# PCA9536.net
KiCad netlist of a schematic drawn in EAGLE
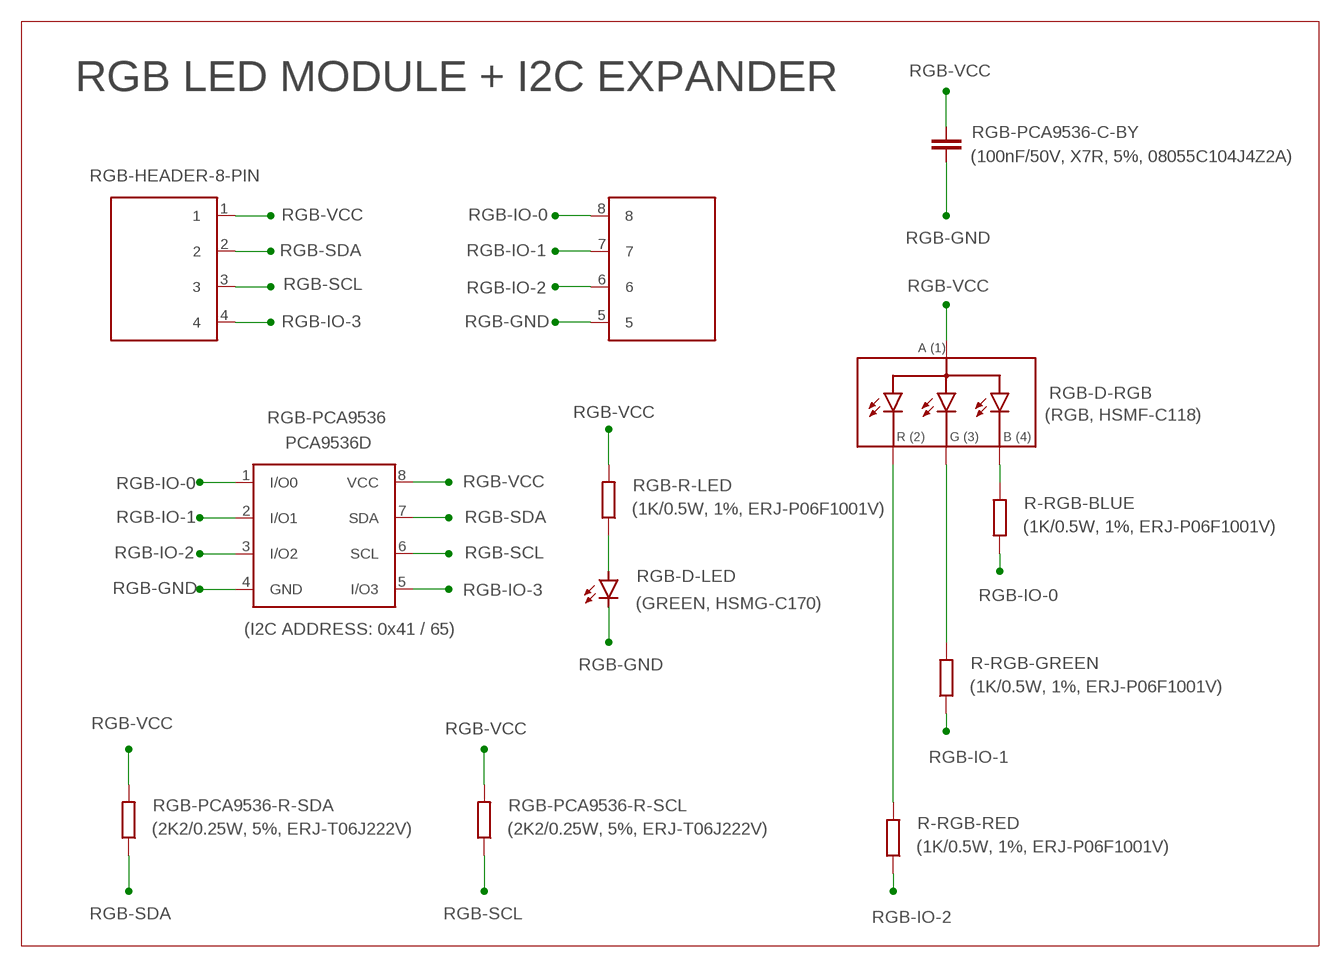
[diagram p0: schematic, sheet 1]

(export (version "E")
  (design (tool "Eeschema 10.0.6"))
  (components
    (comp (ref "R-RGB-BLUE")
      (value "(1K/0.5W, 1%, ERJ-P06F1001V)")
      (footprint "eagle-import:0805")
      (libsource (lib "eagle-import") (part "ERJ-P06F1001V"))
    )
    (comp (ref "R-RGB-GREEN")
      (value "(1K/0.5W, 1%, ERJ-P06F1001V)")
      (footprint "eagle-import:0805")
      (libsource (lib "eagle-import") (part "ERJ-P06F1001V"))
    )
    (comp (ref "R-RGB-RED")
      (value "(1K/0.5W, 1%, ERJ-P06F1001V)")
      (footprint "eagle-import:0805")
      (libsource (lib "eagle-import") (part "ERJ-P06F1001V"))
    )
    (comp (ref "RGB-D-LED")
      (value "(GREEN, HSMG-C170)")
      (footprint "eagle-import:DIODE_0805")
      (libsource (lib "eagle-import") (part "HSMG-C170"))
    )
    (comp (ref "RGB-D-RGB")
      (value "(RGB, HSMF-C118)")
      (footprint "eagle-import:DIODE_LED_1210_RGB")
      (libsource (lib "eagle-import") (part "HSMF-C118"))
    )
    (comp (ref "RGB-J1")
      (value "RGB-HEADER-8-PIN")
      (footprint "eagle-import:HEADER_2.54MM_8_PIN_VER")
      (libsource (lib "eagle-import") (part "HEADER_8_PIN"))
    )
    (comp (ref "RGB-PCA9536")
      (value "PCA9536D")
      (footprint "eagle-import:SOIC-8-NARROW")
      (libsource (lib "eagle-import") (part "PCA9536D"))
    )
    (comp (ref "RGB-PCA9536-C-BY")
      (value "(100nF/50V, X7R, 5%, 08055C104J4Z2A)")
      (footprint "eagle-import:0805")
      (libsource (lib "eagle-import") (part "08055C104J4Z2A"))
    )
    (comp (ref "RGB-PCA9536-R-SCL")
      (value "(2K2/0.25W, 5%, ERJ-T06J222V)")
      (footprint "eagle-import:0805")
      (libsource (lib "eagle-import") (part "ERJ-T06J222V"))
    )
    (comp (ref "RGB-PCA9536-R-SDA")
      (value "(2K2/0.25W, 5%, ERJ-T06J222V)")
      (footprint "eagle-import:0805")
      (libsource (lib "eagle-import") (part "ERJ-T06J222V"))
    )
    (comp (ref "RGB-R-LED")
      (value "(1K/0.5W, 1%, ERJ-P06F1001V)")
      (footprint "eagle-import:0805")
      (libsource (lib "eagle-import") (part "ERJ-P06F1001V"))
    )
  )
  (nets
    (net (code "1") (name "/RGB-GND") (class "Default")
      (node (ref "RGB-D-LED") (pin "C") (pinfunction "C_C") (pintype "passive"))
      (node (ref "RGB-J1") (pin "5") (pinfunction "5_5") (pintype "bidirectional"))
      (node (ref "RGB-PCA9536") (pin "4") (pinfunction "GND_4") (pintype "power_in"))
      (node (ref "RGB-PCA9536-C-BY") (pin "1") (pinfunction "A_1") (pintype "passive"))
    )
    (net (code "2") (name "/RGB-IO-0") (class "Default")
      (node (ref "R-RGB-BLUE") (pin "1") (pinfunction "1_1") (pintype "passive"))
      (node (ref "RGB-J1") (pin "8") (pinfunction "8_8") (pintype "bidirectional"))
      (node (ref "RGB-PCA9536") (pin "1") (pinfunction "I/O0_1") (pintype "bidirectional"))
    )
    (net (code "3") (name "/RGB-IO-1") (class "Default")
      (node (ref "R-RGB-GREEN") (pin "1") (pinfunction "1_1") (pintype "passive"))
      (node (ref "RGB-J1") (pin "7") (pinfunction "7_7") (pintype "bidirectional"))
      (node (ref "RGB-PCA9536") (pin "2") (pinfunction "I/O1_2") (pintype "bidirectional"))
    )
    (net (code "4") (name "/RGB-IO-2") (class "Default")
      (node (ref "R-RGB-RED") (pin "1") (pinfunction "1_1") (pintype "passive"))
      (node (ref "RGB-J1") (pin "6") (pinfunction "6_6") (pintype "bidirectional"))
      (node (ref "RGB-PCA9536") (pin "3") (pinfunction "I/O2_3") (pintype "bidirectional"))
    )
    (net (code "5") (name "/RGB-IO-3") (class "Default")
      (node (ref "RGB-J1") (pin "4") (pinfunction "4_4") (pintype "bidirectional"))
      (node (ref "RGB-PCA9536") (pin "5") (pinfunction "I/O3_5") (pintype "bidirectional"))
    )
    (net (code "6") (name "/RGB-SCL") (class "Default")
      (node (ref "RGB-J1") (pin "3") (pinfunction "3_3") (pintype "bidirectional"))
      (node (ref "RGB-PCA9536") (pin "6") (pinfunction "SCL_6") (pintype "bidirectional"))
      (node (ref "RGB-PCA9536-R-SCL") (pin "1") (pinfunction "1_1") (pintype "passive"))
    )
    (net (code "7") (name "/RGB-SDA") (class "Default")
      (node (ref "RGB-J1") (pin "2") (pinfunction "2_2") (pintype "bidirectional"))
      (node (ref "RGB-PCA9536") (pin "7") (pinfunction "SDA_7") (pintype "bidirectional"))
      (node (ref "RGB-PCA9536-R-SDA") (pin "1") (pinfunction "1_1") (pintype "passive"))
    )
    (net (code "8") (name "/RGB-VCC") (class "Default")
      (node (ref "RGB-D-RGB") (pin "1") (pinfunction "1_1") (pintype "passive"))
      (node (ref "RGB-J1") (pin "1") (pinfunction "1_1") (pintype "bidirectional"))
      (node (ref "RGB-PCA9536") (pin "8") (pinfunction "VCC_8") (pintype "power_in"))
      (node (ref "RGB-PCA9536-C-BY") (pin "2") (pinfunction "C_2") (pintype "passive"))
      (node (ref "RGB-PCA9536-R-SCL") (pin "2") (pinfunction "2_2") (pintype "passive"))
      (node (ref "RGB-PCA9536-R-SDA") (pin "2") (pinfunction "2_2") (pintype "passive"))
      (node (ref "RGB-R-LED") (pin "2") (pinfunction "2_2") (pintype "passive"))
    )
    (net (code "9") (name "Net-(R-RGB-BLUE-Pad2)") (class "Default")
      (node (ref "R-RGB-BLUE") (pin "2") (pinfunction "2_2") (pintype "passive"))
      (node (ref "RGB-D-RGB") (pin "4") (pinfunction "4_4") (pintype "passive"))
    )
    (net (code "10") (name "Net-(R-RGB-GREEN-Pad2)") (class "Default")
      (node (ref "R-RGB-GREEN") (pin "2") (pinfunction "2_2") (pintype "passive"))
      (node (ref "RGB-D-RGB") (pin "3") (pinfunction "3_3") (pintype "passive"))
    )
    (net (code "11") (name "Net-(R-RGB-RED-Pad2)") (class "Default")
      (node (ref "R-RGB-RED") (pin "2") (pinfunction "2_2") (pintype "passive"))
      (node (ref "RGB-D-RGB") (pin "2") (pinfunction "2_2") (pintype "passive"))
    )
    (net (code "12") (name "Net-(RGB-D-LED-PadA)") (class "Default")
      (node (ref "RGB-D-LED") (pin "A") (pinfunction "A_A") (pintype "passive"))
      (node (ref "RGB-R-LED") (pin "1") (pinfunction "1_1") (pintype "passive"))
    )
  )
)
